# Wifi_Board_Rework.net
KiCad netlist of a schematic drawn in EAGLE
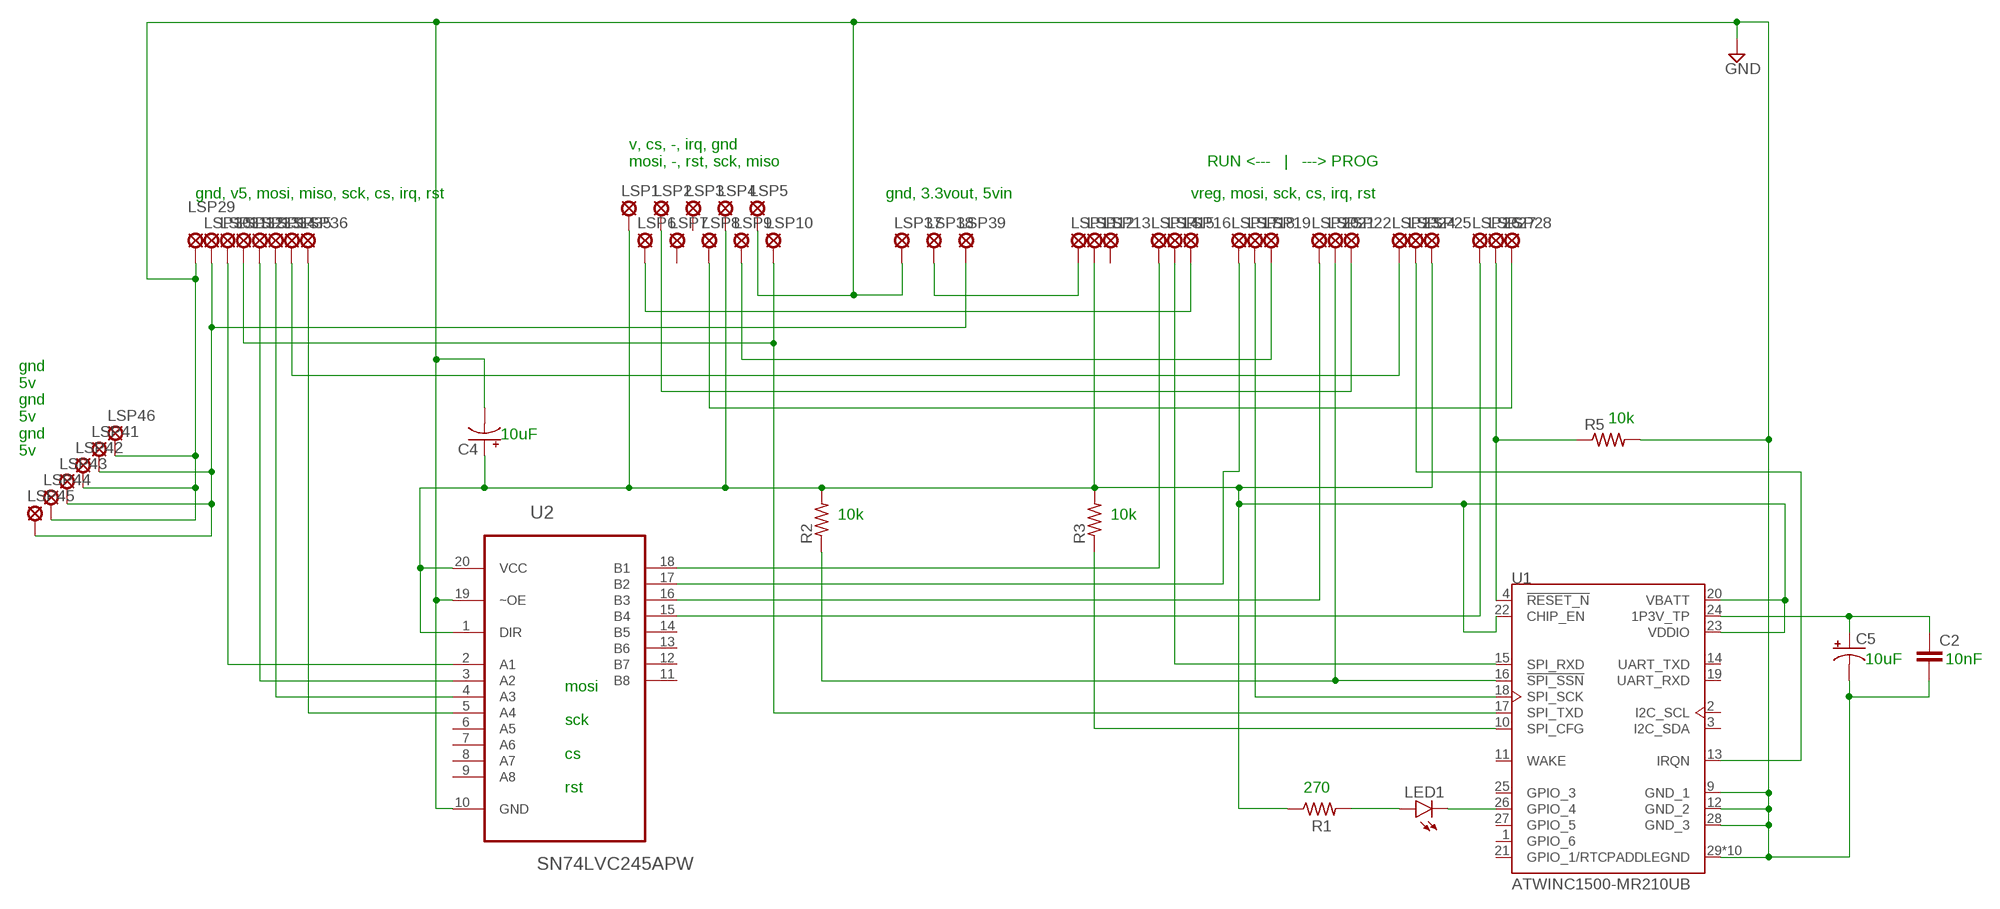
[diagram p0: schematic, sheet 1]

(export (version "E")
  (design (tool "Eeschema 10.0.6"))
  (components
    (comp (ref "C2")
      (value "C5/2.5")
      (footprint "eagle-import:C5B2.5")
      (libsource (lib "eagle-import") (part "C5/2.5"))
    )
    (comp (ref "C4")
      (value "CPOL-USE2-4")
      (footprint "eagle-import:E2-4")
      (libsource (lib "eagle-import") (part "CPOL-USE2-4"))
    )
    (comp (ref "C5")
      (value "CPOL-USE2-4")
      (footprint "eagle-import:E2-4")
      (libsource (lib "eagle-import") (part "CPOL-USE2-4"))
    )
    (comp (ref "LED1")
      (value "LED5MM")
      (footprint "eagle-import:LED5MM")
      (libsource (lib "eagle-import") (part "LED5MM"))
    )
    (comp (ref "LSP1")
      (value "LSP10_CLSP10_C")
      (footprint "eagle-import:LSP10_C")
      (libsource (lib "eagle-import") (part "LSP10_CLSP10_C"))
    )
    (comp (ref "LSP2")
      (value "LSP10_CLSP10_C")
      (footprint "eagle-import:LSP10_C")
      (libsource (lib "eagle-import") (part "LSP10_CLSP10_C"))
    )
    (comp (ref "LSP3")
      (value "LSP10_CLSP10_C")
      (footprint "eagle-import:LSP10_C")
      (libsource (lib "eagle-import") (part "LSP10_CLSP10_C"))
    )
    (comp (ref "LSP4")
      (value "LSP10_CLSP10_C")
      (footprint "eagle-import:LSP10_C")
      (libsource (lib "eagle-import") (part "LSP10_CLSP10_C"))
    )
    (comp (ref "LSP5")
      (value "LSP10_CLSP10_C")
      (footprint "eagle-import:LSP10_C")
      (libsource (lib "eagle-import") (part "LSP10_CLSP10_C"))
    )
    (comp (ref "LSP6")
      (value "LSP10_S")
      (footprint "eagle-import:LSP10_S")
      (libsource (lib "eagle-import") (part "LSP10_S"))
    )
    (comp (ref "LSP7")
      (value "LSP10_CLSP10_C")
      (footprint "eagle-import:LSP10_C")
      (libsource (lib "eagle-import") (part "LSP10_CLSP10_C"))
    )
    (comp (ref "LSP8")
      (value "LSP10_CLSP10_C")
      (footprint "eagle-import:LSP10_C")
      (libsource (lib "eagle-import") (part "LSP10_CLSP10_C"))
    )
    (comp (ref "LSP9")
      (value "LSP10_CLSP10_C")
      (footprint "eagle-import:LSP10_C")
      (libsource (lib "eagle-import") (part "LSP10_CLSP10_C"))
    )
    (comp (ref "LSP10")
      (value "LSP10_CLSP10_C")
      (footprint "eagle-import:LSP10_C")
      (libsource (lib "eagle-import") (part "LSP10_CLSP10_C"))
    )
    (comp (ref "LSP11")
      (value "LSP10_CLSP10_C")
      (footprint "eagle-import:LSP10_C")
      (libsource (lib "eagle-import") (part "LSP10_CLSP10_C"))
    )
    (comp (ref "LSP12")
      (value "LSP10_CLSP10_C")
      (footprint "eagle-import:LSP10_C")
      (libsource (lib "eagle-import") (part "LSP10_CLSP10_C"))
    )
    (comp (ref "LSP13")
      (value "LSP10_CLSP10_C")
      (footprint "eagle-import:LSP10_C")
      (libsource (lib "eagle-import") (part "LSP10_CLSP10_C"))
    )
    (comp (ref "LSP14")
      (value "LSP10_CLSP10_C")
      (footprint "eagle-import:LSP10_C")
      (libsource (lib "eagle-import") (part "LSP10_CLSP10_C"))
    )
    (comp (ref "LSP15")
      (value "LSP10_CLSP10_C")
      (footprint "eagle-import:LSP10_C")
      (libsource (lib "eagle-import") (part "LSP10_CLSP10_C"))
    )
    (comp (ref "LSP16")
      (value "LSP10_CLSP10_C")
      (footprint "eagle-import:LSP10_C")
      (libsource (lib "eagle-import") (part "LSP10_CLSP10_C"))
    )
    (comp (ref "LSP17")
      (value "LSP10_CLSP10_C")
      (footprint "eagle-import:LSP10_C")
      (libsource (lib "eagle-import") (part "LSP10_CLSP10_C"))
    )
    (comp (ref "LSP18")
      (value "LSP10_CLSP10_C")
      (footprint "eagle-import:LSP10_C")
      (libsource (lib "eagle-import") (part "LSP10_CLSP10_C"))
    )
    (comp (ref "LSP19")
      (value "LSP10_CLSP10_C")
      (footprint "eagle-import:LSP10_C")
      (libsource (lib "eagle-import") (part "LSP10_CLSP10_C"))
    )
    (comp (ref "LSP20")
      (value "LSP10_CLSP10_C")
      (footprint "eagle-import:LSP10_C")
      (libsource (lib "eagle-import") (part "LSP10_CLSP10_C"))
    )
    (comp (ref "LSP21")
      (value "LSP10_CLSP10_C")
      (footprint "eagle-import:LSP10_C")
      (libsource (lib "eagle-import") (part "LSP10_CLSP10_C"))
    )
    (comp (ref "LSP22")
      (value "LSP10_CLSP10_C")
      (footprint "eagle-import:LSP10_C")
      (libsource (lib "eagle-import") (part "LSP10_CLSP10_C"))
    )
    (comp (ref "LSP23")
      (value "LSP10_CLSP10_C")
      (footprint "eagle-import:LSP10_C")
      (libsource (lib "eagle-import") (part "LSP10_CLSP10_C"))
    )
    (comp (ref "LSP24")
      (value "LSP10_CLSP10_C")
      (footprint "eagle-import:LSP10_C")
      (libsource (lib "eagle-import") (part "LSP10_CLSP10_C"))
    )
    (comp (ref "LSP25")
      (value "LSP10_CLSP10_C")
      (footprint "eagle-import:LSP10_C")
      (libsource (lib "eagle-import") (part "LSP10_CLSP10_C"))
    )
    (comp (ref "LSP26")
      (value "LSP10_CLSP10_C")
      (footprint "eagle-import:LSP10_C")
      (libsource (lib "eagle-import") (part "LSP10_CLSP10_C"))
    )
    (comp (ref "LSP27")
      (value "LSP10_CLSP10_C")
      (footprint "eagle-import:LSP10_C")
      (libsource (lib "eagle-import") (part "LSP10_CLSP10_C"))
    )
    (comp (ref "LSP28")
      (value "LSP10_CLSP10_C")
      (footprint "eagle-import:LSP10_C")
      (libsource (lib "eagle-import") (part "LSP10_CLSP10_C"))
    )
    (comp (ref "LSP29")
      (value "LSP10_S")
      (footprint "eagle-import:LSP10_S")
      (libsource (lib "eagle-import") (part "LSP10_S"))
    )
    (comp (ref "LSP30")
      (value "LSP10_CLSP10_C")
      (footprint "eagle-import:LSP10_C")
      (libsource (lib "eagle-import") (part "LSP10_CLSP10_C"))
    )
    (comp (ref "LSP31")
      (value "LSP10_CLSP10_C")
      (footprint "eagle-import:LSP10_C")
      (libsource (lib "eagle-import") (part "LSP10_CLSP10_C"))
    )
    (comp (ref "LSP32")
      (value "LSP10_CLSP10_C")
      (footprint "eagle-import:LSP10_C")
      (libsource (lib "eagle-import") (part "LSP10_CLSP10_C"))
    )
    (comp (ref "LSP33")
      (value "LSP10_CLSP10_C")
      (footprint "eagle-import:LSP10_C")
      (libsource (lib "eagle-import") (part "LSP10_CLSP10_C"))
    )
    (comp (ref "LSP34")
      (value "LSP10_CLSP10_C")
      (footprint "eagle-import:LSP10_C")
      (libsource (lib "eagle-import") (part "LSP10_CLSP10_C"))
    )
    (comp (ref "LSP35")
      (value "LSP10_CLSP10_C")
      (footprint "eagle-import:LSP10_C")
      (libsource (lib "eagle-import") (part "LSP10_CLSP10_C"))
    )
    (comp (ref "LSP36")
      (value "LSP10_CLSP10_C")
      (footprint "eagle-import:LSP10_C")
      (libsource (lib "eagle-import") (part "LSP10_CLSP10_C"))
    )
    (comp (ref "LSP37")
      (value "LSP10_S")
      (footprint "eagle-import:LSP10_S")
      (libsource (lib "eagle-import") (part "LSP10_S"))
    )
    (comp (ref "LSP38")
      (value "LSP10_CLSP10_C")
      (footprint "eagle-import:LSP10_C")
      (libsource (lib "eagle-import") (part "LSP10_CLSP10_C"))
    )
    (comp (ref "LSP39")
      (value "LSP10_CLSP10_C")
      (footprint "eagle-import:LSP10_C")
      (libsource (lib "eagle-import") (part "LSP10_CLSP10_C"))
    )
    (comp (ref "LSP41")
      (value "LSP10_CLSP10_C")
      (footprint "eagle-import:LSP10_C")
      (libsource (lib "eagle-import") (part "LSP10_CLSP10_C"))
    )
    (comp (ref "LSP42")
      (value "LSP10_CLSP10_C")
      (footprint "eagle-import:LSP10_C")
      (libsource (lib "eagle-import") (part "LSP10_CLSP10_C"))
    )
    (comp (ref "LSP43")
      (value "LSP10_CLSP10_C")
      (footprint "eagle-import:LSP10_C")
      (libsource (lib "eagle-import") (part "LSP10_CLSP10_C"))
    )
    (comp (ref "LSP44")
      (value "LSP10_CLSP10_C")
      (footprint "eagle-import:LSP10_C")
      (libsource (lib "eagle-import") (part "LSP10_CLSP10_C"))
    )
    (comp (ref "LSP45")
      (value "LSP10_CLSP10_C")
      (footprint "eagle-import:LSP10_C")
      (libsource (lib "eagle-import") (part "LSP10_CLSP10_C"))
    )
    (comp (ref "LSP46")
      (value "LSP10_S")
      (footprint "eagle-import:LSP10_S")
      (libsource (lib "eagle-import") (part "LSP10_S"))
    )
    (comp (ref "R1")
      (value "R-US_VMTA55")
      (footprint "eagle-import:VMTA55")
      (libsource (lib "eagle-import") (part "R-US_VMTA55"))
    )
    (comp (ref "R2")
      (value "R-US_VMTA55")
      (footprint "eagle-import:VMTA55")
      (libsource (lib "eagle-import") (part "R-US_VMTA55"))
    )
    (comp (ref "R3")
      (value "R-US_VMTA55")
      (footprint "eagle-import:VMTA55")
      (libsource (lib "eagle-import") (part "R-US_VMTA55"))
    )
    (comp (ref "R5")
      (value "R-US_VMTA55")
      (footprint "eagle-import:VMTA55")
      (libsource (lib "eagle-import") (part "R-US_VMTA55"))
    )
    (comp (ref "U1")
      (value "ATWINC1500-MR210UB")
      (footprint "eagle-import:MICROCHIP_ATWINC1500-MR210UB")
      (fields (field (name "MF") "Microchip"))
      (libsource (lib "eagle-import") (part "ATWINC1500-MR210UB"))
    )
    (comp (ref "U2")
      (value "SN74LVC245APW")
      (footprint "eagle-import:SOP65P640X120-20N")
      (fields (field (name "MF") "Texas Instruments"))
      (libsource (lib "eagle-import") (part "SN74LVC245APW"))
    )
  )
  (nets
    (net (code "1") (name "GND") (class "Default")
      (node (ref "C2") (pin "2") (pinfunction "2_2") (pintype "passive"))
      (node (ref "C4") (pin "-") (pinfunction "-_-") (pintype "passive"))
      (node (ref "C5") (pin "-") (pinfunction "-_-") (pintype "passive"))
      (node (ref "LSP29") (pin "P$1") (pinfunction "MP_P$1") (pintype "passive"))
      (node (ref "LSP37") (pin "P$1") (pinfunction "MP_P$1") (pintype "passive"))
      (node (ref "LSP42") (pin "P$1") (pinfunction "MP_P$1") (pintype "passive"))
      (node (ref "LSP44") (pin "P$1") (pinfunction "MP_P$1") (pintype "passive"))
      (node (ref "LSP46") (pin "P$1") (pinfunction "MP_P$1") (pintype "passive"))
      (node (ref "LSP5") (pin "P$1") (pinfunction "MP_P$1") (pintype "passive"))
      (node (ref "R5") (pin "2") (pinfunction "2_2") (pintype "passive"))
      (node (ref "U1") (pin "12") (pinfunction "GND_2_12") (pintype "power_in"))
      (node (ref "U1") (pin "28") (pinfunction "GND_3_28") (pintype "power_in"))
      (node (ref "U1") (pin "29") (pinfunction "PADDLEGND_29") (pintype "power_in"))
      (node (ref "U1") (pin "9") (pinfunction "GND_1_9") (pintype "power_in"))
      (node (ref "U1") (pin "P$1") (pinfunction "PADDLEGND_P$1") (pintype "power_in"))
      (node (ref "U1") (pin "P$2") (pinfunction "PADDLEGND_P$2") (pintype "power_in"))
      (node (ref "U1") (pin "P$3") (pinfunction "PADDLEGND_P$3") (pintype "power_in"))
      (node (ref "U1") (pin "P$4") (pinfunction "PADDLEGND_P$4") (pintype "power_in"))
      (node (ref "U1") (pin "P$5") (pinfunction "PADDLEGND_P$5") (pintype "power_in"))
      (node (ref "U1") (pin "P$6") (pinfunction "PADDLEGND_P$6") (pintype "power_in"))
      (node (ref "U1") (pin "P$7") (pinfunction "PADDLEGND_P$7") (pintype "power_in"))
      (node (ref "U1") (pin "P$8") (pinfunction "PADDLEGND_P$8") (pintype "power_in"))
      (node (ref "U1") (pin "P$9") (pinfunction "PADDLEGND_P$9") (pintype "power_in"))
      (node (ref "U2") (pin "10") (pinfunction "GND_10") (pintype "passive"))
      (node (ref "U2") (pin "19") (pinfunction "~{OE}_19") (pintype "input"))
    )
    (net (code "2") (name "Net-(LED1-C)") (class "Default")
      (node (ref "LED1") (pin "K") (pinfunction "C_K") (pintype "passive"))
      (node (ref "U1") (pin "26") (pinfunction "GPIO_4_26") (pintype "bidirectional"))
    )
    (net (code "3") (name "Net-(LED1-PadA)") (class "Default")
      (node (ref "LED1") (pin "A") (pinfunction "A_A") (pintype "passive"))
      (node (ref "R1") (pin "2") (pinfunction "2_2") (pintype "passive"))
    )
    (net (code "4") (name "Net-(LSP1-MP)") (class "Default")
      (node (ref "C4") (pin "+") (pinfunction "+_+") (pintype "passive"))
      (node (ref "LSP1") (pin "P$1") (pinfunction "MP_P$1") (pintype "passive"))
      (node (ref "LSP12") (pin "P$1") (pinfunction "MP_P$1") (pintype "passive"))
      (node (ref "LSP25") (pin "P$1") (pinfunction "MP_P$1") (pintype "passive"))
      (node (ref "LSP4") (pin "P$1") (pinfunction "MP_P$1") (pintype "passive"))
      (node (ref "R1") (pin "1") (pinfunction "1_1") (pintype "passive"))
      (node (ref "R2") (pin "2") (pinfunction "2_2") (pintype "passive"))
      (node (ref "R3") (pin "2") (pinfunction "2_2") (pintype "passive"))
      (node (ref "U1") (pin "20") (pinfunction "VBATT_20") (pintype "power_in"))
      (node (ref "U1") (pin "22") (pinfunction "CHIP_EN_22") (pintype "input"))
      (node (ref "U1") (pin "23") (pinfunction "VDDIO_23") (pintype "power_in"))
      (node (ref "U2") (pin "1") (pinfunction "DIR_1") (pintype "input"))
      (node (ref "U2") (pin "20") (pinfunction "VCC_20") (pintype "power_in"))
    )
    (net (code "5") (name "Net-(LSP2-MP)") (class "Default")
      (node (ref "LSP2") (pin "P$1") (pinfunction "MP_P$1") (pintype "passive"))
      (node (ref "LSP22") (pin "P$1") (pinfunction "MP_P$1") (pintype "passive"))
    )
    (net (code "6") (name "Net-(LSP10-MP)") (class "Default")
      (node (ref "LSP10") (pin "P$1") (pinfunction "MP_P$1") (pintype "passive"))
      (node (ref "LSP32") (pin "P$1") (pinfunction "MP_P$1") (pintype "passive"))
      (node (ref "U1") (pin "17") (pinfunction "SPI_TXD_17") (pintype "output"))
    )
    (net (code "7") (name "Net-(LSP11-MP)") (class "Default")
      (node (ref "LSP11") (pin "P$1") (pinfunction "MP_P$1") (pintype "passive"))
      (node (ref "LSP38") (pin "P$1") (pinfunction "MP_P$1") (pintype "passive"))
    )
    (net (code "8") (name "Net-(LSP14-MP)") (class "Default")
      (node (ref "LSP14") (pin "P$1") (pinfunction "MP_P$1") (pintype "passive"))
      (node (ref "U2") (pin "18") (pinfunction "B1_18") (pintype "bidirectional"))
    )
    (net (code "9") (name "Net-(LSP15-MP)") (class "Default")
      (node (ref "LSP15") (pin "P$1") (pinfunction "MP_P$1") (pintype "passive"))
      (node (ref "U1") (pin "15") (pinfunction "SPI_RXD_15") (pintype "input"))
    )
    (net (code "10") (name "Net-(LSP16-MP)") (class "Default")
      (node (ref "LSP16") (pin "P$1") (pinfunction "MP_P$1") (pintype "passive"))
      (node (ref "LSP6") (pin "P$1") (pinfunction "MP_P$1") (pintype "passive"))
    )
    (net (code "11") (name "Net-(LSP17-MP)") (class "Default")
      (node (ref "LSP17") (pin "P$1") (pinfunction "MP_P$1") (pintype "passive"))
      (node (ref "U2") (pin "17") (pinfunction "B2_17") (pintype "bidirectional"))
    )
    (net (code "12") (name "Net-(LSP18-MP)") (class "Default")
      (node (ref "LSP18") (pin "P$1") (pinfunction "MP_P$1") (pintype "passive"))
      (node (ref "U1") (pin "18") (pinfunction "SPI_SCK_18") (pintype "input"))
    )
    (net (code "13") (name "Net-(LSP19-MP)") (class "Default")
      (node (ref "LSP19") (pin "P$1") (pinfunction "MP_P$1") (pintype "passive"))
      (node (ref "LSP9") (pin "P$1") (pinfunction "MP_P$1") (pintype "passive"))
    )
    (net (code "14") (name "Net-(LSP20-MP)") (class "Default")
      (node (ref "LSP20") (pin "P$1") (pinfunction "MP_P$1") (pintype "passive"))
      (node (ref "U2") (pin "16") (pinfunction "B3_16") (pintype "bidirectional"))
    )
    (net (code "15") (name "Net-(LSP21-MP)") (class "Default")
      (node (ref "LSP21") (pin "P$1") (pinfunction "MP_P$1") (pintype "passive"))
      (node (ref "R2") (pin "1") (pinfunction "1_1") (pintype "passive"))
      (node (ref "U1") (pin "16") (pinfunction "~{SPI_SSN}_16") (pintype "input"))
    )
    (net (code "16") (name "Net-(LSP23-MP)") (class "Default")
      (node (ref "LSP23") (pin "P$1") (pinfunction "MP_P$1") (pintype "passive"))
      (node (ref "LSP35") (pin "P$1") (pinfunction "MP_P$1") (pintype "passive"))
    )
    (net (code "17") (name "Net-(LSP24-MP)") (class "Default")
      (node (ref "LSP24") (pin "P$1") (pinfunction "MP_P$1") (pintype "passive"))
      (node (ref "U1") (pin "13") (pinfunction "IRQN_13") (pintype "output"))
    )
    (net (code "18") (name "Net-(LSP26-MP)") (class "Default")
      (node (ref "LSP26") (pin "P$1") (pinfunction "MP_P$1") (pintype "passive"))
      (node (ref "U2") (pin "15") (pinfunction "B4_15") (pintype "bidirectional"))
    )
    (net (code "19") (name "Net-(LSP27-MP)") (class "Default")
      (node (ref "LSP27") (pin "P$1") (pinfunction "MP_P$1") (pintype "passive"))
      (node (ref "R5") (pin "1") (pinfunction "1_1") (pintype "passive"))
      (node (ref "U1") (pin "4") (pinfunction "~{RESET_N}_4") (pintype "input"))
    )
    (net (code "20") (name "Net-(LSP28-MP)") (class "Default")
      (node (ref "LSP28") (pin "P$1") (pinfunction "MP_P$1") (pintype "passive"))
      (node (ref "LSP8") (pin "P$1") (pinfunction "MP_P$1") (pintype "passive"))
    )
    (net (code "21") (name "Net-(LSP30-MP)") (class "Default")
      (node (ref "LSP30") (pin "P$1") (pinfunction "MP_P$1") (pintype "passive"))
      (node (ref "LSP39") (pin "P$1") (pinfunction "MP_P$1") (pintype "passive"))
      (node (ref "LSP41") (pin "P$1") (pinfunction "MP_P$1") (pintype "passive"))
      (node (ref "LSP43") (pin "P$1") (pinfunction "MP_P$1") (pintype "passive"))
      (node (ref "LSP45") (pin "P$1") (pinfunction "MP_P$1") (pintype "passive"))
    )
    (net (code "22") (name "Net-(LSP31-MP)") (class "Default")
      (node (ref "LSP31") (pin "P$1") (pinfunction "MP_P$1") (pintype "passive"))
      (node (ref "U2") (pin "2") (pinfunction "A1_2") (pintype "bidirectional"))
    )
    (net (code "23") (name "Net-(LSP33-MP)") (class "Default")
      (node (ref "LSP33") (pin "P$1") (pinfunction "MP_P$1") (pintype "passive"))
      (node (ref "U2") (pin "3") (pinfunction "A2_3") (pintype "bidirectional"))
    )
    (net (code "24") (name "Net-(LSP34-MP)") (class "Default")
      (node (ref "LSP34") (pin "P$1") (pinfunction "MP_P$1") (pintype "passive"))
      (node (ref "U2") (pin "4") (pinfunction "A3_4") (pintype "bidirectional"))
    )
    (net (code "25") (name "Net-(LSP36-MP)") (class "Default")
      (node (ref "LSP36") (pin "P$1") (pinfunction "MP_P$1") (pintype "passive"))
      (node (ref "U2") (pin "5") (pinfunction "A4_5") (pintype "bidirectional"))
    )
    (net (code "26") (name "Net-(U1-1P3V_TP)") (class "Default")
      (node (ref "C2") (pin "1") (pinfunction "1_1") (pintype "passive"))
      (node (ref "C5") (pin "+") (pinfunction "+_+") (pintype "passive"))
      (node (ref "U1") (pin "24") (pinfunction "1P3V_TP_24") (pintype "power_in"))
    )
    (net (code "27") (name "Net-(U1-SPI_CFG)") (class "Default")
      (node (ref "R3") (pin "1") (pinfunction "1_1") (pintype "passive"))
      (node (ref "U1") (pin "10") (pinfunction "SPI_CFG_10") (pintype "input"))
    )
    (net (code "28") (name "unconnected-(LSP3-MP-PadP$1)") (class "Default")
      (node (ref "LSP3") (pin "P$1") (pinfunction "MP_P$1") (pintype "passive"))
    )
    (net (code "29") (name "unconnected-(LSP7-MP-PadP$1)") (class "Default")
      (node (ref "LSP7") (pin "P$1") (pinfunction "MP_P$1") (pintype "passive"))
    )
    (net (code "30") (name "unconnected-(LSP13-MP-PadP$1)") (class "Default")
      (node (ref "LSP13") (pin "P$1") (pinfunction "MP_P$1") (pintype "passive"))
    )
    (net (code "31") (name "unconnected-(U1-GPIO_1{slash}RTC-Pad21)") (class "Default")
      (node (ref "U1") (pin "21") (pinfunction "GPIO_1/RTC_21") (pintype "input"))
    )
    (net (code "32") (name "unconnected-(U1-GPIO_3-Pad25)") (class "Default")
      (node (ref "U1") (pin "25") (pinfunction "GPIO_3_25") (pintype "bidirectional"))
    )
    (net (code "33") (name "unconnected-(U1-GPIO_5-Pad27)") (class "Default")
      (node (ref "U1") (pin "27") (pinfunction "GPIO_5_27") (pintype "bidirectional"))
    )
    (net (code "34") (name "unconnected-(U1-GPIO_6-Pad1)") (class "Default")
      (node (ref "U1") (pin "1") (pinfunction "GPIO_6_1") (pintype "bidirectional"))
    )
    (net (code "35") (name "unconnected-(U1-I2C_SCL-Pad2)") (class "Default")
      (node (ref "U1") (pin "2") (pinfunction "I2C_SCL_2") (pintype "bidirectional"))
    )
    (net (code "36") (name "unconnected-(U1-I2C_SDA-Pad3)") (class "Default")
      (node (ref "U1") (pin "3") (pinfunction "I2C_SDA_3") (pintype "bidirectional"))
    )
    (net (code "37") (name "unconnected-(U1-UART_RXD-Pad19)") (class "Default")
      (node (ref "U1") (pin "19") (pinfunction "UART_RXD_19") (pintype "input"))
    )
    (net (code "38") (name "unconnected-(U1-UART_TXD-Pad14)") (class "Default")
      (node (ref "U1") (pin "14") (pinfunction "UART_TXD_14") (pintype "output"))
    )
    (net (code "39") (name "unconnected-(U1-WAKE-Pad11)") (class "Default")
      (node (ref "U1") (pin "11") (pinfunction "WAKE_11") (pintype "input"))
    )
    (net (code "40") (name "unconnected-(U2-A5-Pad6)") (class "Default")
      (node (ref "U2") (pin "6") (pinfunction "A5_6") (pintype "bidirectional"))
    )
    (net (code "41") (name "unconnected-(U2-A6-Pad7)") (class "Default")
      (node (ref "U2") (pin "7") (pinfunction "A6_7") (pintype "bidirectional"))
    )
    (net (code "42") (name "unconnected-(U2-A7-Pad8)") (class "Default")
      (node (ref "U2") (pin "8") (pinfunction "A7_8") (pintype "bidirectional"))
    )
    (net (code "43") (name "unconnected-(U2-A8-Pad9)") (class "Default")
      (node (ref "U2") (pin "9") (pinfunction "A8_9") (pintype "bidirectional"))
    )
    (net (code "44") (name "unconnected-(U2-B5-Pad14)") (class "Default")
      (node (ref "U2") (pin "14") (pinfunction "B5_14") (pintype "bidirectional"))
    )
    (net (code "45") (name "unconnected-(U2-B6-Pad13)") (class "Default")
      (node (ref "U2") (pin "13") (pinfunction "B6_13") (pintype "bidirectional"))
    )
    (net (code "46") (name "unconnected-(U2-B7-Pad12)") (class "Default")
      (node (ref "U2") (pin "12") (pinfunction "B7_12") (pintype "bidirectional"))
    )
    (net (code "47") (name "unconnected-(U2-B8-Pad11)") (class "Default")
      (node (ref "U2") (pin "11") (pinfunction "B8_11") (pintype "bidirectional"))
    )
  )
)
